# avruler_touch.net
KiCad netlist of a schematic drawn in EAGLE
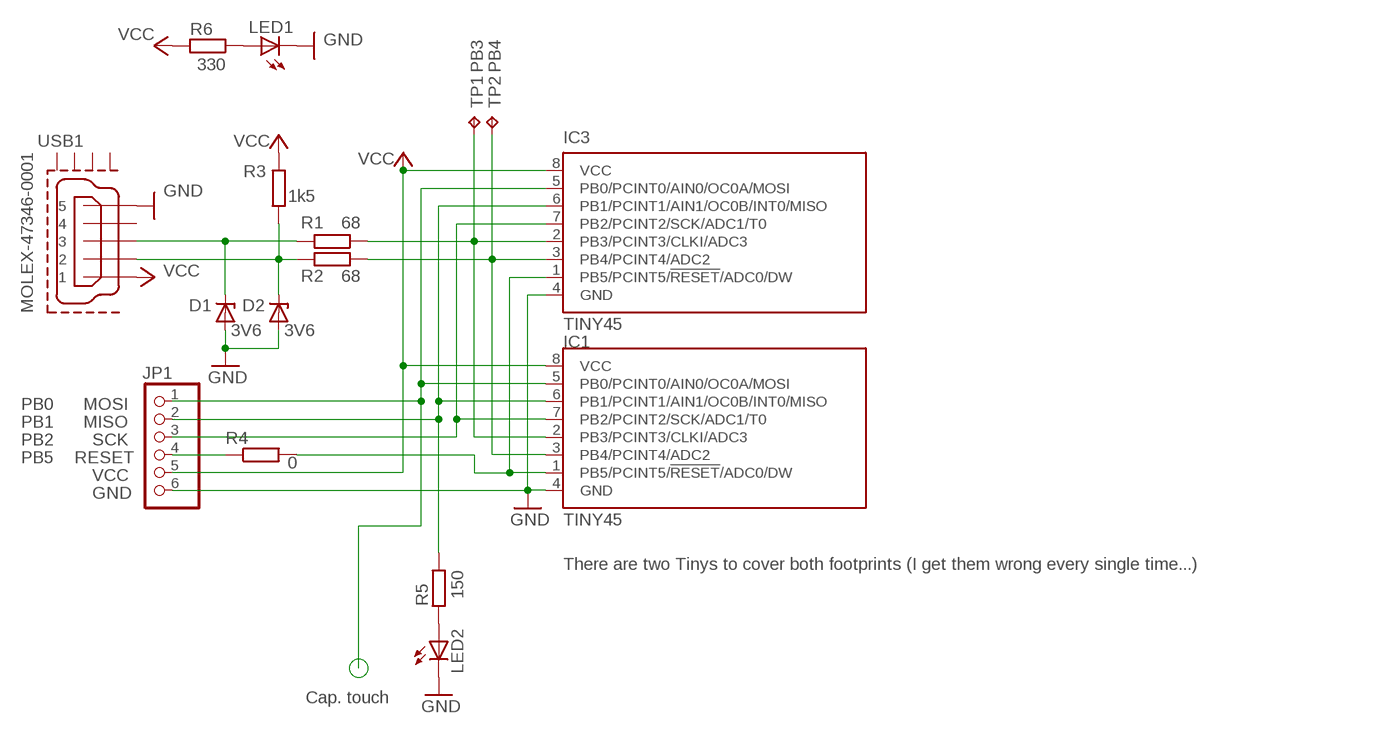
[diagram p0: schematic, sheet 1]

(export (version "E")
  (design (tool "Eeschema 10.0.6"))
  (components
    (comp (ref "D1")
      (value "3V6")
      (footprint "eagle-import:SOD80C")
      (libsource (lib "eagle-import") (part "ZENER-DIODESOD80C"))
    )
    (comp (ref "D2")
      (value "3V6")
      (footprint "eagle-import:SOD80C")
      (libsource (lib "eagle-import") (part "ZENER-DIODESOD80C"))
    )
    (comp (ref "IC1")
      (value "TINY45")
      (footprint "eagle-import:8S1")
      (fields (field (name "MPN") "ATTINY13-20SSU"))
      (libsource (lib "eagle-import") (part "TINY13SSU-20"))
    )
    (comp (ref "IC3")
      (value "TINY45")
      (footprint "eagle-import:8S2")
      (fields (field (name "MPN") "ATTINY13-20SU"))
      (libsource (lib "eagle-import") (part "TINY13SU-20"))
    )
    (comp (ref "JP1")
      (value "PINHD-1X6/90")
      (footprint "eagle-import:1X06_90")
      (libsource (lib "eagle-import") (part "PINHD-1X6/90"))
    )
    (comp (ref "LED1")
      (value "LEDCHIPLED_1206")
      (footprint "eagle-import:CHIPLED_1206")
      (libsource (lib "eagle-import") (part "LEDCHIPLED_1206"))
    )
    (comp (ref "LED2")
      (value "LEDCHIPLED_1206")
      (footprint "eagle-import:CHIPLED_1206")
      (libsource (lib "eagle-import") (part "LEDCHIPLED_1206"))
    )
    (comp (ref "R1")
      (value "68")
      (footprint "eagle-import:M1206")
      (libsource (lib "eagle-import") (part "R-EU_M1206"))
    )
    (comp (ref "R2")
      (value "68")
      (footprint "eagle-import:M1206")
      (libsource (lib "eagle-import") (part "R-EU_M1206"))
    )
    (comp (ref "R3")
      (value "1k5")
      (footprint "eagle-import:M1206")
      (libsource (lib "eagle-import") (part "R-EU_M1206"))
    )
    (comp (ref "R4")
      (value "0")
      (footprint "eagle-import:M1206")
      (libsource (lib "eagle-import") (part "R-EU_M1206"))
    )
    (comp (ref "R5")
      (value "150")
      (footprint "eagle-import:M1206")
      (libsource (lib "eagle-import") (part "R-EU_M1206"))
    )
    (comp (ref "R6")
      (value "330")
      (footprint "eagle-import:M1206")
      (libsource (lib "eagle-import") (part "R-EU_M1206"))
    )
    (comp (ref "TP1")
      (value "TPTP14SQ")
      (footprint "eagle-import:TP14SQ")
      (libsource (lib "eagle-import") (part "TPTP14SQ"))
    )
    (comp (ref "TP2")
      (value "TPTP14SQ")
      (footprint "eagle-import:TP14SQ")
      (libsource (lib "eagle-import") (part "TPTP14SQ"))
    )
    (comp (ref "USB1")
      (value "MOLEX-47346-0001")
      (footprint "eagle-import:MOLEX-47364-0001")
      (libsource (lib "eagle-import") (part "MOLEX-47346-0001"))
    )
  )
  (nets
    (net (code "1") (name "GND") (class "Default")
      (node (ref "D1") (pin "A") (pinfunction "A_A") (pintype "passive"))
      (node (ref "D2") (pin "A") (pinfunction "A_A") (pintype "passive"))
      (node (ref "IC1") (pin "4") (pinfunction "GND_4") (pintype "power_in"))
      (node (ref "IC3") (pin "4") (pinfunction "GND_4") (pintype "power_in"))
      (node (ref "JP1") (pin "6") (pinfunction "6_6") (pintype "passive"))
      (node (ref "LED1") (pin "C") (pinfunction "C_C") (pintype "passive"))
      (node (ref "LED2") (pin "C") (pinfunction "C_C") (pintype "passive"))
      (node (ref "USB1") (pin "5") (pinfunction "5_5") (pintype "input"))
    )
    (net (code "2") (name "Net-(D1-PadC)") (class "Default")
      (node (ref "D1") (pin "C") (pinfunction "C_C") (pintype "passive"))
      (node (ref "R1") (pin "2") (pinfunction "2_2") (pintype "passive"))
      (node (ref "USB1") (pin "3") (pinfunction "3_3") (pintype "input"))
    )
    (net (code "3") (name "Net-(D2-PadC)") (class "Default")
      (node (ref "D2") (pin "C") (pinfunction "C_C") (pintype "passive"))
      (node (ref "R2") (pin "2") (pinfunction "2_2") (pintype "passive"))
      (node (ref "R3") (pin "2") (pinfunction "2_2") (pintype "passive"))
      (node (ref "USB1") (pin "2") (pinfunction "2_2") (pintype "input"))
    )
    (net (code "4") (name "Net-(IC1-PB0{slash}PCINT0{slash}AIN0{slash}OC0A{slash}MOSI)") (class "Default")
      (node (ref "IC1") (pin "5") (pinfunction "PB0/PCINT0/AIN0/OC0A/MOSI_5") (pintype "bidirectional"))
      (node (ref "IC3") (pin "5") (pinfunction "PB0/PCINT0/AIN0/OC0A/MOSI_5") (pintype "bidirectional"))
      (node (ref "JP1") (pin "1") (pinfunction "1_1") (pintype "passive"))
    )
    (net (code "5") (name "Net-(IC1-PB1{slash}PCINT1{slash}AIN1{slash}OC0B{slash}INT0{slash}MISO)") (class "Default")
      (node (ref "IC1") (pin "6") (pinfunction "PB1/PCINT1/AIN1/OC0B/INT0/MISO_6") (pintype "bidirectional"))
      (node (ref "IC3") (pin "6") (pinfunction "PB1/PCINT1/AIN1/OC0B/INT0/MISO_6") (pintype "bidirectional"))
      (node (ref "JP1") (pin "2") (pinfunction "2_2") (pintype "passive"))
      (node (ref "R5") (pin "1") (pinfunction "1_1") (pintype "passive"))
    )
    (net (code "6") (name "Net-(IC1-PB2{slash}PCINT2{slash}SCK{slash}ADC1{slash}T0)") (class "Default")
      (node (ref "IC1") (pin "7") (pinfunction "PB2/PCINT2/SCK/ADC1/T0_7") (pintype "bidirectional"))
      (node (ref "IC3") (pin "7") (pinfunction "PB2/PCINT2/SCK/ADC1/T0_7") (pintype "bidirectional"))
      (node (ref "JP1") (pin "3") (pinfunction "3_3") (pintype "passive"))
    )
    (net (code "7") (name "Net-(IC1-PB3{slash}PCINT3{slash}CLKI{slash}ADC3)") (class "Default")
      (node (ref "IC1") (pin "2") (pinfunction "PB3/PCINT3/CLKI/ADC3_2") (pintype "bidirectional"))
      (node (ref "IC3") (pin "2") (pinfunction "PB3/PCINT3/CLKI/ADC3_2") (pintype "bidirectional"))
      (node (ref "R1") (pin "1") (pinfunction "1_1") (pintype "passive"))
      (node (ref "TP1") (pin "TP") (pinfunction "TP_TP") (pintype "input"))
    )
    (net (code "8") (name "Net-(IC1-PB4{slash}PCINT4{slash}ADC2)") (class "Default")
      (node (ref "IC1") (pin "3") (pinfunction "PB4/PCINT4/ADC2_3") (pintype "bidirectional"))
      (node (ref "IC3") (pin "3") (pinfunction "PB4/PCINT4/ADC2_3") (pintype "bidirectional"))
      (node (ref "R2") (pin "1") (pinfunction "1_1") (pintype "passive"))
      (node (ref "TP2") (pin "TP") (pinfunction "TP_TP") (pintype "input"))
    )
    (net (code "9") (name "Net-(IC1-PB5{slash}PCINT5{slash}~{RESET}{slash}ADC0{slash}DW)") (class "Default")
      (node (ref "IC1") (pin "1") (pinfunction "PB5/PCINT5/~{RESET}/ADC0/DW_1") (pintype "bidirectional"))
      (node (ref "IC3") (pin "1") (pinfunction "PB5/PCINT5/~{RESET}/ADC0/DW_1") (pintype "bidirectional"))
      (node (ref "R4") (pin "2") (pinfunction "2_2") (pintype "passive"))
    )
    (net (code "10") (name "Net-(JP1-Pad4)") (class "Default")
      (node (ref "JP1") (pin "4") (pinfunction "4_4") (pintype "passive"))
      (node (ref "R4") (pin "1") (pinfunction "1_1") (pintype "passive"))
    )
    (net (code "11") (name "Net-(LED1-PadA)") (class "Default")
      (node (ref "LED1") (pin "A") (pinfunction "A_A") (pintype "passive"))
      (node (ref "R6") (pin "1") (pinfunction "1_1") (pintype "passive"))
    )
    (net (code "12") (name "Net-(LED2-PadA)") (class "Default")
      (node (ref "LED2") (pin "A") (pinfunction "A_A") (pintype "passive"))
      (node (ref "R5") (pin "2") (pinfunction "2_2") (pintype "passive"))
    )
    (net (code "13") (name "VCC") (class "Default")
      (node (ref "IC1") (pin "8") (pinfunction "VCC_8") (pintype "power_in"))
      (node (ref "IC3") (pin "8") (pinfunction "VCC_8") (pintype "power_in"))
      (node (ref "JP1") (pin "5") (pinfunction "5_5") (pintype "passive"))
      (node (ref "R3") (pin "1") (pinfunction "1_1") (pintype "passive"))
      (node (ref "R6") (pin "2") (pinfunction "2_2") (pintype "passive"))
      (node (ref "USB1") (pin "1") (pinfunction "1_1") (pintype "input"))
    )
    (net (code "14") (name "unconnected-(USB1-Pad4)") (class "Default")
      (node (ref "USB1") (pin "4") (pinfunction "4_4") (pintype "input"))
    )
    (net (code "15") (name "unconnected-(USB1-PadGND1)") (class "Default")
      (node (ref "USB1") (pin "GND1") (pinfunction "GND1_GND1") (pintype "bidirectional"))
    )
    (net (code "16") (name "unconnected-(USB1-PadGND2)") (class "Default")
      (node (ref "USB1") (pin "GND2") (pinfunction "GND2_GND2") (pintype "bidirectional"))
    )
    (net (code "17") (name "unconnected-(USB1-PadGND3)") (class "Default")
      (node (ref "USB1") (pin "GND3") (pinfunction "GND3_GND3") (pintype "bidirectional"))
    )
    (net (code "18") (name "unconnected-(USB1-PadGND4)") (class "Default")
      (node (ref "USB1") (pin "GND4") (pinfunction "GND4_GND4") (pintype "bidirectional"))
    )
  )
)
